# Sheet1.net
KiCad netlist of a schematic drawn in Altium Designer
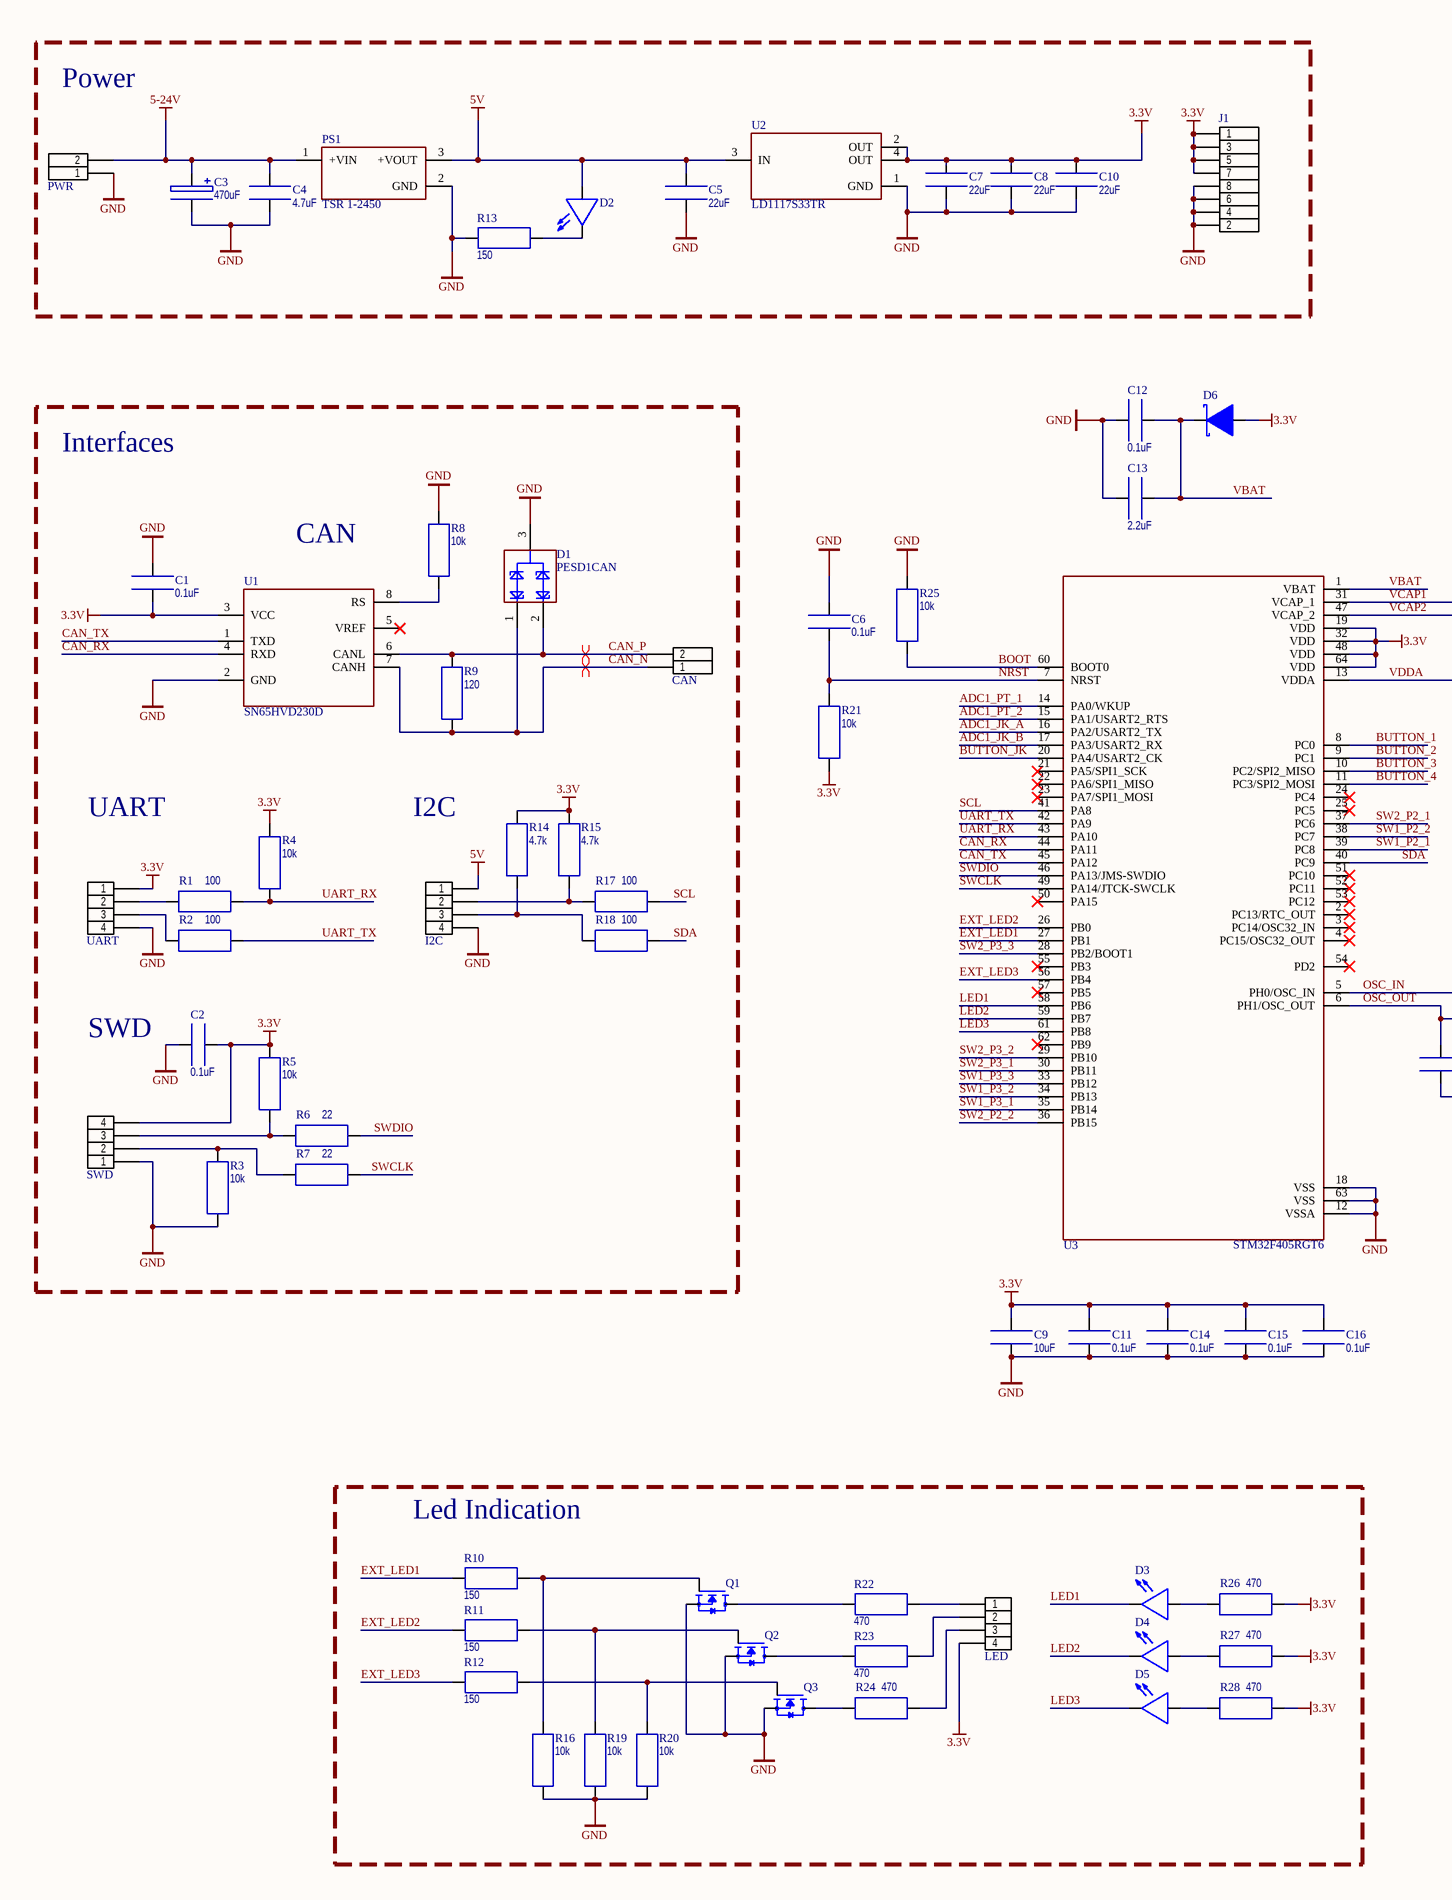
[diagram p0: Sheet1.SchDoc, left]
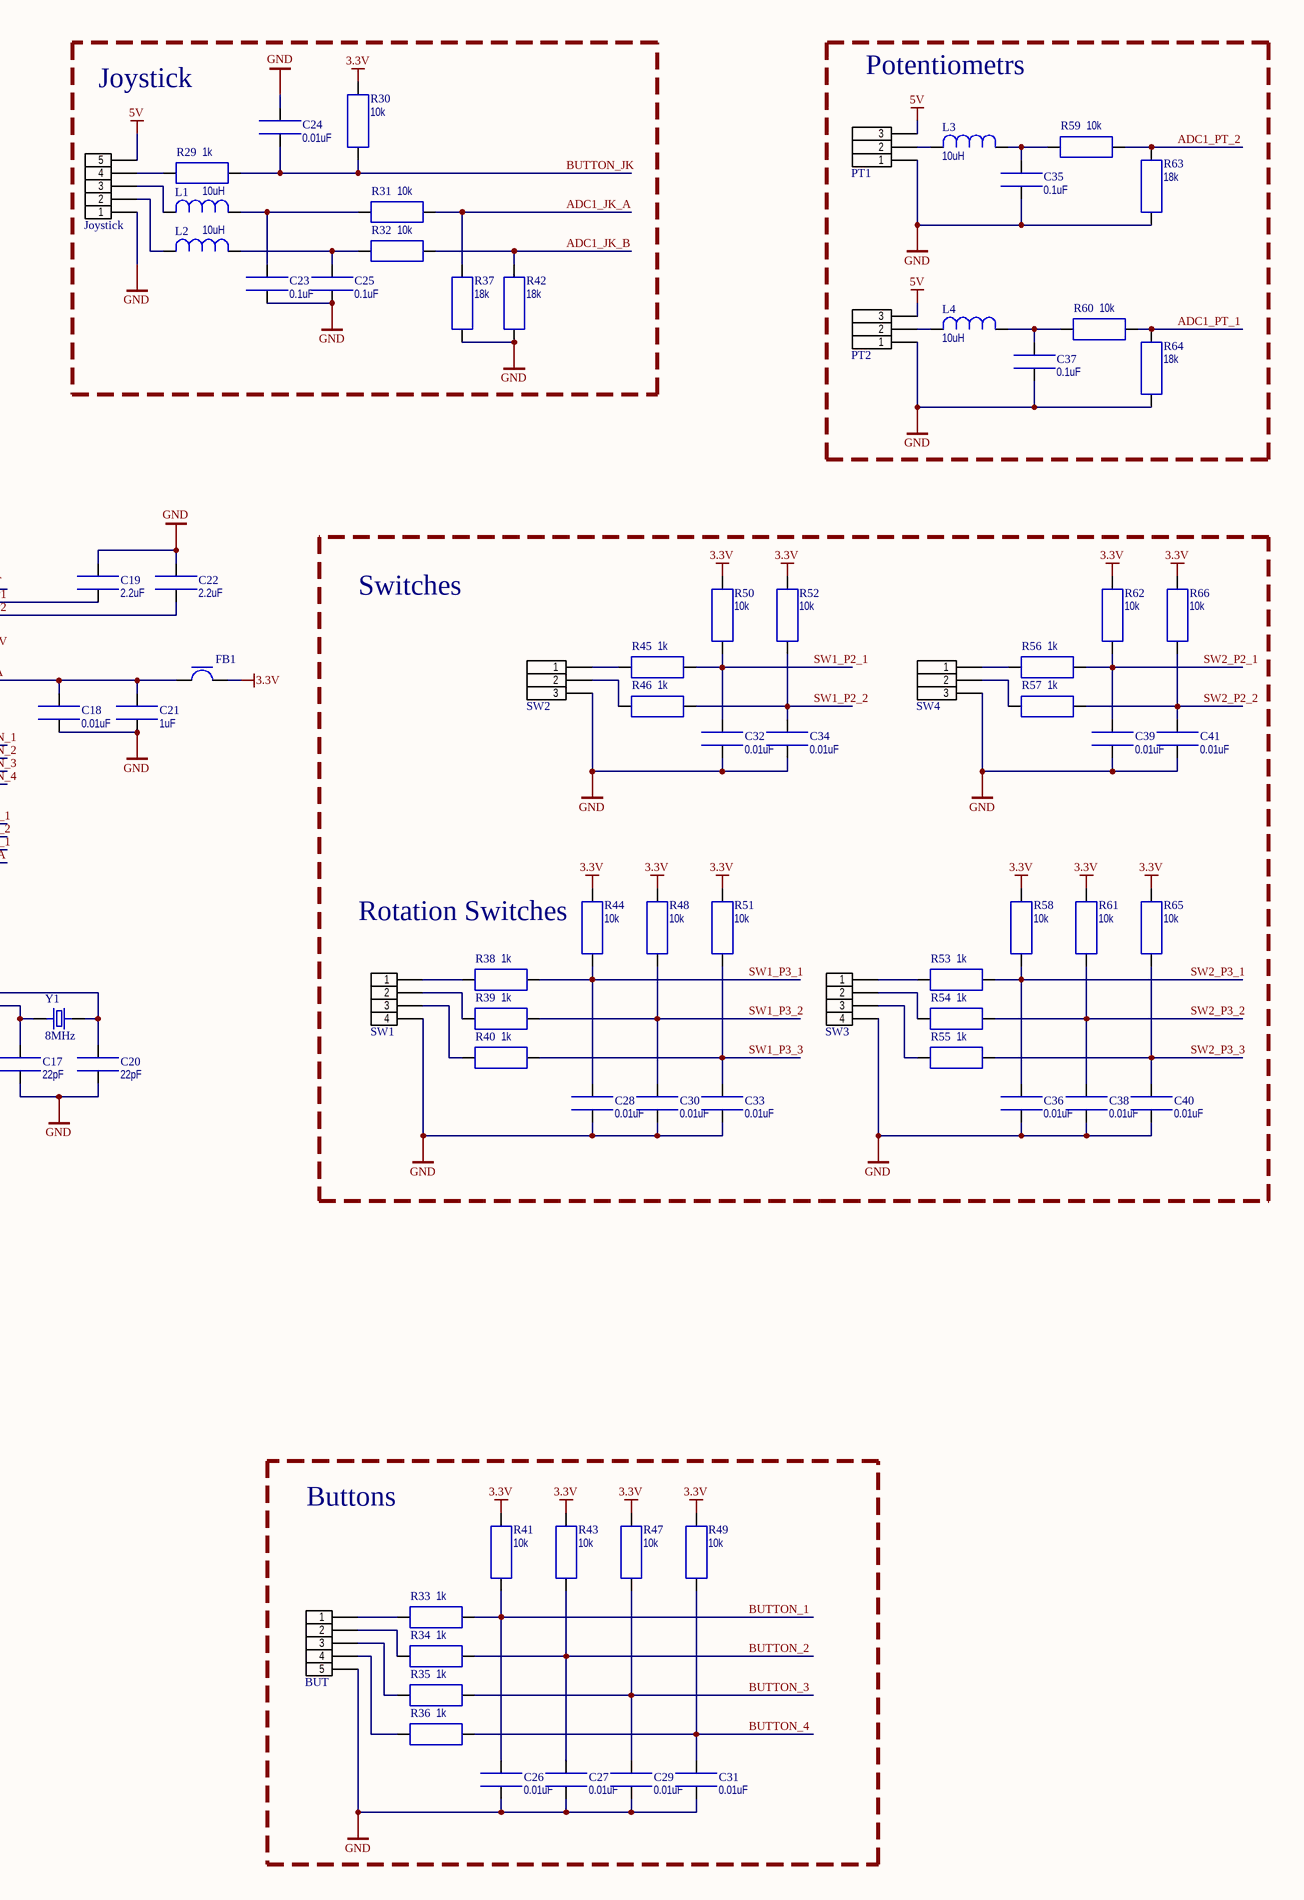
[diagram p1: Sheet1.SchDoc, right]

(export (version "E")
  (design (tool "Eeschema 10.0.6"))
  (components
    (comp (ref "BUT")
      (value "B5B-XH-A")
      (footprint "JST_B5B-XH-A")
      (description "Connector Header Through Hole 5 position 0.098 (2.50mm)")
      (fields (field (name "MF") "JST Sales"))
      (libsource (lib "connector") (part "B5B-XH-A"))
    )
    (comp (ref "C1") (value "0.1uF") (footprint "CAP 0603") (libsource (lib "passive") (part "CAP 0603")))
    (comp (ref "C2") (value "0.1uF") (footprint "CAP 0603") (libsource (lib "passive") (part "CAP 0603")))
    (comp (ref "C3") (value "470uF") (footprint "ECAP G") (libsource (lib "passive") (part "ECAP")))
    (comp (ref "C4") (value "4.7uF") (footprint "CAP 0603") (libsource (lib "passive") (part "CAP 0603")))
    (comp (ref "C5") (value "22uF") (footprint "CAP 0805") (libsource (lib "passive") (part "CAP 0805")))
    (comp (ref "C6") (value "0.1uF") (footprint "CAP 0603") (libsource (lib "passive") (part "CAP 0603")))
    (comp (ref "C7") (value "22uF") (footprint "CAP 0805") (libsource (lib "passive") (part "CAP 0805")))
    (comp (ref "C8") (value "22uF") (footprint "CAP 0805") (libsource (lib "passive") (part "CAP 0805")))
    (comp (ref "C9") (value "10uF") (footprint "CAP 0805") (libsource (lib "passive") (part "CAP 0805")))
    (comp (ref "C10") (value "22uF") (footprint "CAP 0805") (libsource (lib "passive") (part "CAP 0805")))
    (comp (ref "C11") (value "0.1uF") (footprint "CAP 0603") (libsource (lib "passive") (part "CAP 0603")))
    (comp (ref "C12") (value "0.1uF") (footprint "CAP 0603") (libsource (lib "passive") (part "CAP 0603")))
    (comp (ref "C13") (value "2.2uF") (footprint "CAP 0603") (libsource (lib "passive") (part "CAP 0603")))
    (comp (ref "C14") (value "0.1uF") (footprint "CAP 0603") (libsource (lib "passive") (part "CAP 0603")))
    (comp (ref "C15") (value "0.1uF") (footprint "CAP 0603") (libsource (lib "passive") (part "CAP 0603")))
    (comp (ref "C16") (value "0.1uF") (footprint "CAP 0603") (libsource (lib "passive") (part "CAP 0603")))
    (comp (ref "C17") (value "22pF") (footprint "CAP 0603") (libsource (lib "passive") (part "CAP 0603")))
    (comp (ref "C18") (value "0.01uF") (footprint "CAP 0603") (libsource (lib "passive") (part "CAP 0603")))
    (comp (ref "C19") (value "2.2uF") (footprint "CAP 0603") (libsource (lib "passive") (part "CAP 0603")))
    (comp (ref "C20") (value "22pF") (footprint "CAP 0603") (libsource (lib "passive") (part "CAP 0603")))
    (comp (ref "C21") (value "1uF") (footprint "CAP 0603") (libsource (lib "passive") (part "CAP 0603")))
    (comp (ref "C22") (value "2.2uF") (footprint "CAP 0603") (libsource (lib "passive") (part "CAP 0603")))
    (comp (ref "C23") (value "0.1uF") (footprint "CAP 0603") (libsource (lib "passive") (part "CAP 0603")))
    (comp (ref "C24") (value "0.01uF") (footprint "CAP 0603") (libsource (lib "passive") (part "CAP 0603")))
    (comp (ref "C25") (value "0.1uF") (footprint "CAP 0603") (libsource (lib "passive") (part "CAP 0603")))
    (comp (ref "C26") (value "0.01uF") (footprint "CAP 0603") (libsource (lib "passive") (part "CAP 0603")))
    (comp (ref "C27") (value "0.01uF") (footprint "CAP 0603") (libsource (lib "passive") (part "CAP 0603")))
    (comp (ref "C28") (value "0.01uF") (footprint "CAP 0603") (libsource (lib "passive") (part "CAP 0603")))
    (comp (ref "C29") (value "0.01uF") (footprint "CAP 0603") (libsource (lib "passive") (part "CAP 0603")))
    (comp (ref "C30") (value "0.01uF") (footprint "CAP 0603") (libsource (lib "passive") (part "CAP 0603")))
    (comp (ref "C31") (value "0.01uF") (footprint "CAP 0603") (libsource (lib "passive") (part "CAP 0603")))
    (comp (ref "C32") (value "0.01uF") (footprint "CAP 0603") (libsource (lib "passive") (part "CAP 0603")))
    (comp (ref "C33") (value "0.01uF") (footprint "CAP 0603") (libsource (lib "passive") (part "CAP 0603")))
    (comp (ref "C34") (value "0.01uF") (footprint "CAP 0603") (libsource (lib "passive") (part "CAP 0603")))
    (comp (ref "C35") (value "0.1uF") (footprint "CAP 0603") (libsource (lib "passive") (part "CAP 0603")))
    (comp (ref "C36") (value "0.01uF") (footprint "CAP 0603") (libsource (lib "passive") (part "CAP 0603")))
    (comp (ref "C37") (value "0.1uF") (footprint "CAP 0603") (libsource (lib "passive") (part "CAP 0603")))
    (comp (ref "C38") (value "0.01uF") (footprint "CAP 0603") (libsource (lib "passive") (part "CAP 0603")))
    (comp (ref "C39") (value "0.01uF") (footprint "CAP 0603") (libsource (lib "passive") (part "CAP 0603")))
    (comp (ref "C40") (value "0.01uF") (footprint "CAP 0603") (libsource (lib "passive") (part "CAP 0603")))
    (comp (ref "C41") (value "0.01uF") (footprint "CAP 0603") (libsource (lib "passive") (part "CAP 0603")))
    (comp (ref "CAN")
      (value "B2B-XH-A")
      (footprint "JST_B2B-XH-A")
      (description "Connector Header Through Hole 2 position 0.098 (2.50mm)")
      (fields (field (name "MF") "JST Sales") (field (name "MP") "B2B-XH-A(LF)(SN)"))
      (libsource (lib "connector") (part "B2B-XH-A"))
    )
    (comp (ref "D1")
      (value "PESD1CAN")
      (footprint "SOT23-3")
      (description "50V Clamp 3A (8/20Âµs) Ipp Tvs Diode Surface Mount SOT-323")
      (fields (field (name "MF") "Nexperia USA"))
      (libsource (lib "active") (part "PESD1CAN"))
    )
    (comp (ref "D2")
      (value "LED 0603")
      (footprint "LED 0603")
      (description "Green 560nm LED Indication - Discrete 2.2V 0603 (1608 Metric)")
      (fields (field (name "MF") "Rohm") (field (name "MP") "SML-D12P8WT86"))
      (libsource (lib "") (part "LED 0603_1"))
    )
    (comp (ref "D3")
      (value "LED 0603")
      (footprint "LED 0603")
      (description "Green 560nm LED Indication - Discrete 2.2V 0603 (1608 Metric)")
      (fields (field (name "MF") "Rohm") (field (name "MP") "SML-D12P8WT86"))
      (libsource (lib "active") (part "LED 0603"))
    )
    (comp (ref "D4")
      (value "LED 0603")
      (footprint "LED 0603")
      (description "Green 560nm LED Indication - Discrete 2.2V 0603 (1608 Metric)")
      (fields (field (name "MF") "Rohm") (field (name "MP") "SML-D12P8WT86"))
      (libsource (lib "active") (part "LED 0603"))
    )
    (comp (ref "D5")
      (value "LED 0603")
      (footprint "LED 0603")
      (description "Green 560nm LED Indication - Discrete 2.2V 0603 (1608 Metric)")
      (fields (field (name "MF") "Rohm") (field (name "MP") "SML-D12P8WT86"))
      (libsource (lib "active") (part "LED 0603"))
    )
    (comp (ref "D6")
      (value "SM5819PL")
      (footprint "SOD-123FL")
      (description "Schottky Diode, 40V, 1A")
      (libsource (lib "active") (part "SM5819PL"))
    )
    (comp (ref "FB1")
      (value "Ferrite bead 0603")
      (footprint "Ferrite bead 0603")
      (libsource (lib "passive") (part "Ferrite bead 0603"))
    )
    (comp (ref "I2C")
      (value "B4B-XH-A")
      (footprint "JST_B4B-XH-A")
      (description "Connector Header Through Hole 4 position 0.098 (2.50mm)")
      (fields (field (name "MF") "JST Sales"))
      (libsource (lib "connector") (part "B4B-XH-A"))
    )
    (comp (ref "J1")
      (value "Pin Header 2x4")
      (footprint "Pin Header 2x4")
      (description "Connector Header Through Hole 8 position 0.100 (2.54mm)")
      (fields (field (name "MF") "Samtec") (field (name "MP") "MTSW-104-07-T-D-240-LL"))
      (libsource (lib "connector") (part "Pin Header 2x4"))
    )
    (comp (ref "Joystick")
      (value "B5B-XH-A")
      (footprint "JST_B5B-XH-A")
      (description "Connector Header Through Hole 5 position 0.098 (2.50mm)")
      (fields (field (name "MF") "JST Sales"))
      (libsource (lib "connector") (part "B5B-XH-A"))
    )
    (comp (ref "L1") (value "10uH") (footprint "L 0603") (libsource (lib "passive") (part "L 0603")))
    (comp (ref "L2") (value "10uH") (footprint "L 0603") (libsource (lib "passive") (part "L 0603")))
    (comp (ref "L3") (value "10uH") (footprint "L 0603") (libsource (lib "passive") (part "L 0603")))
    (comp (ref "L4") (value "10uH") (footprint "L 0603") (libsource (lib "passive") (part "L 0603")))
    (comp (ref "LED")
      (value "B4B-XH-A")
      (footprint "JST_B4B-XH-A")
      (description "Connector Header Through Hole 4 position 0.098 (2.50mm)")
      (fields (field (name "MF") "JST Sales"))
      (libsource (lib "connector") (part "B4B-XH-A"))
    )
    (comp (ref "PS1")
      (value "TSR 1-2450")
      (footprint "SIP3")
      (fields (field (name "MF") "Traco Power") (field (name "MP") "TSR_1-2450"))
      (libsource (lib "mcu") (part "TSR 1-2450"))
    )
    (comp (ref "PT1")
      (value "B3B-XH-A")
      (footprint "JST_B3B-XH-A")
      (description "Connector Header Through Hole 3 position 0.098 (2.50mm)")
      (fields (field (name "MF") "JST Sales"))
      (libsource (lib "connector") (part "B3B-XH-A"))
    )
    (comp (ref "PT2")
      (value "B3B-XH-A")
      (footprint "JST_B3B-XH-A")
      (description "Connector Header Through Hole 3 position 0.098 (2.50mm)")
      (fields (field (name "MF") "JST Sales"))
      (libsource (lib "connector") (part "B3B-XH-A"))
    )
    (comp (ref "PWR")
      (value "B2B-XH-A")
      (footprint "JST_B2B-XH-A")
      (description "Connector Header Through Hole 2 position 0.098 (2.50mm)")
      (fields (field (name "MF") "JST Sales") (field (name "MP") "B2B-XH-A(LF)(SN)"))
      (libsource (lib "") (part "B2B-XH-A_1"))
    )
    (comp (ref "Q1")
      (value "MMFTN20")
      (footprint "SOT23-3")
      (description "MOSFET, SOT-23, N, 50V, 0.1A, 15â„¦, 150Â°C")
      (fields (field (name "MF") "Diotec Semiconductor"))
      (libsource (lib "active") (part "MMFTN20"))
    )
    (comp (ref "Q2")
      (value "MMFTN20")
      (footprint "SOT23-3")
      (description "MOSFET, SOT-23, N, 50V, 0.1A, 15â„¦, 150Â°C")
      (fields (field (name "MF") "Diotec Semiconductor"))
      (libsource (lib "active") (part "MMFTN20"))
    )
    (comp (ref "Q3")
      (value "MMFTN20")
      (footprint "SOT23-3")
      (description "MOSFET, SOT-23, N, 50V, 0.1A, 15â„¦, 150Â°C")
      (fields (field (name "MF") "Diotec Semiconductor"))
      (libsource (lib "active") (part "MMFTN20"))
    )
    (comp (ref "R1") (value "100") (footprint "RES 0603") (libsource (lib "passive") (part "RES 0603")))
    (comp (ref "R2") (value "100") (footprint "RES 0603") (libsource (lib "passive") (part "RES 0603")))
    (comp (ref "R3") (value "10k") (footprint "RES 0603") (libsource (lib "passive") (part "RES 0603")))
    (comp (ref "R4") (value "10k") (footprint "RES 0603") (libsource (lib "passive") (part "RES 0603")))
    (comp (ref "R5") (value "10k") (footprint "RES 0603") (libsource (lib "passive") (part "RES 0603")))
    (comp (ref "R6") (value "22") (footprint "RES 0603") (libsource (lib "passive") (part "RES 0603")))
    (comp (ref "R7") (value "22") (footprint "RES 0603") (libsource (lib "passive") (part "RES 0603")))
    (comp (ref "R8") (value "10k") (footprint "RES 0603") (libsource (lib "passive") (part "RES 0603")))
    (comp (ref "R9") (value "120") (footprint "RES 0603") (libsource (lib "passive") (part "RES 0603")))
    (comp (ref "R10") (value "150") (footprint "RES 0603") (libsource (lib "passive") (part "RES 0603")))
    (comp (ref "R11") (value "150") (footprint "RES 0603") (libsource (lib "passive") (part "RES 0603")))
    (comp (ref "R12") (value "150") (footprint "RES 0603") (libsource (lib "passive") (part "RES 0603")))
    (comp (ref "R13") (value "150") (footprint "RES 0603") (libsource (lib "passive") (part "RES 0603")))
    (comp (ref "R14") (value "4.7k") (footprint "RES 0603") (libsource (lib "passive") (part "RES 0603")))
    (comp (ref "R15") (value "4.7k") (footprint "RES 0603") (libsource (lib "passive") (part "RES 0603")))
    (comp (ref "R16") (value "10k") (footprint "RES 0603") (libsource (lib "passive") (part "RES 0603")))
    (comp (ref "R17") (value "100") (footprint "RES 0603") (libsource (lib "passive") (part "RES 0603")))
    (comp (ref "R18") (value "100") (footprint "RES 0603") (libsource (lib "passive") (part "RES 0603")))
    (comp (ref "R19") (value "10k") (footprint "RES 0603") (libsource (lib "passive") (part "RES 0603")))
    (comp (ref "R20") (value "10k") (footprint "RES 0603") (libsource (lib "passive") (part "RES 0603")))
    (comp (ref "R21") (value "10k") (footprint "RES 0603") (libsource (lib "passive") (part "RES 0603")))
    (comp (ref "R22") (value "470") (footprint "RES 0603") (libsource (lib "passive") (part "RES 0603")))
    (comp (ref "R23") (value "470") (footprint "RES 0603") (libsource (lib "passive") (part "RES 0603")))
    (comp (ref "R24") (value "470") (footprint "RES 0603") (libsource (lib "passive") (part "RES 0603")))
    (comp (ref "R25") (value "10k") (footprint "RES 0603") (libsource (lib "passive") (part "RES 0603")))
    (comp (ref "R26") (value "470") (footprint "RES 0603") (libsource (lib "passive") (part "RES 0603")))
    (comp (ref "R27") (value "470") (footprint "RES 0603") (libsource (lib "passive") (part "RES 0603")))
    (comp (ref "R28") (value "470") (footprint "RES 0603") (libsource (lib "passive") (part "RES 0603")))
    (comp (ref "R29") (value "1k") (footprint "RES 0603") (libsource (lib "passive") (part "RES 0603")))
    (comp (ref "R30") (value "10k") (footprint "RES 0603") (libsource (lib "passive") (part "RES 0603")))
    (comp (ref "R31") (value "10k") (footprint "RES 0603") (libsource (lib "passive") (part "RES 0603")))
    (comp (ref "R32") (value "10k") (footprint "RES 0603") (libsource (lib "passive") (part "RES 0603")))
    (comp (ref "R33") (value "1k") (footprint "RES 0603") (libsource (lib "passive") (part "RES 0603")))
    (comp (ref "R34") (value "1k") (footprint "RES 0603") (libsource (lib "passive") (part "RES 0603")))
    (comp (ref "R35") (value "1k") (footprint "RES 0603") (libsource (lib "passive") (part "RES 0603")))
    (comp (ref "R36") (value "1k") (footprint "RES 0603") (libsource (lib "passive") (part "RES 0603")))
    (comp (ref "R37") (value "18k") (footprint "RES 0603") (libsource (lib "passive") (part "RES 0603")))
    (comp (ref "R38") (value "1k") (footprint "RES 0603") (libsource (lib "passive") (part "RES 0603")))
    (comp (ref "R39") (value "1k") (footprint "RES 0603") (libsource (lib "passive") (part "RES 0603")))
    (comp (ref "R40") (value "1k") (footprint "RES 0603") (libsource (lib "passive") (part "RES 0603")))
    (comp (ref "R41") (value "10k") (footprint "RES 0603") (libsource (lib "passive") (part "RES 0603")))
    (comp (ref "R42") (value "18k") (footprint "RES 0603") (libsource (lib "passive") (part "RES 0603")))
    (comp (ref "R43") (value "10k") (footprint "RES 0603") (libsource (lib "passive") (part "RES 0603")))
    (comp (ref "R44") (value "10k") (footprint "RES 0603") (libsource (lib "passive") (part "RES 0603")))
    (comp (ref "R45") (value "1k") (footprint "RES 0603") (libsource (lib "passive") (part "RES 0603")))
    (comp (ref "R46") (value "1k") (footprint "RES 0603") (libsource (lib "passive") (part "RES 0603")))
    (comp (ref "R47") (value "10k") (footprint "RES 0603") (libsource (lib "passive") (part "RES 0603")))
    (comp (ref "R48") (value "10k") (footprint "RES 0603") (libsource (lib "passive") (part "RES 0603")))
    (comp (ref "R49") (value "10k") (footprint "RES 0603") (libsource (lib "passive") (part "RES 0603")))
    (comp (ref "R50") (value "10k") (footprint "RES 0603") (libsource (lib "passive") (part "RES 0603")))
    (comp (ref "R51") (value "10k") (footprint "RES 0603") (libsource (lib "passive") (part "RES 0603")))
    (comp (ref "R52") (value "10k") (footprint "RES 0603") (libsource (lib "passive") (part "RES 0603")))
    (comp (ref "R53") (value "1k") (footprint "RES 0603") (libsource (lib "passive") (part "RES 0603")))
    (comp (ref "R54") (value "1k") (footprint "RES 0603") (libsource (lib "passive") (part "RES 0603")))
    (comp (ref "R55") (value "1k") (footprint "RES 0603") (libsource (lib "passive") (part "RES 0603")))
    (comp (ref "R56") (value "1k") (footprint "RES 0603") (libsource (lib "passive") (part "RES 0603")))
    (comp (ref "R57") (value "1k") (footprint "RES 0603") (libsource (lib "passive") (part "RES 0603")))
    (comp (ref "R58") (value "10k") (footprint "RES 0603") (libsource (lib "passive") (part "RES 0603")))
    (comp (ref "R59") (value "10k") (footprint "RES 0603") (libsource (lib "passive") (part "RES 0603")))
    (comp (ref "R60") (value "10k") (footprint "RES 0603") (libsource (lib "passive") (part "RES 0603")))
    (comp (ref "R61") (value "10k") (footprint "RES 0603") (libsource (lib "passive") (part "RES 0603")))
    (comp (ref "R62") (value "10k") (footprint "RES 0603") (libsource (lib "passive") (part "RES 0603")))
    (comp (ref "R63") (value "18k") (footprint "RES 0603") (libsource (lib "passive") (part "RES 0603")))
    (comp (ref "R64") (value "18k") (footprint "RES 0603") (libsource (lib "passive") (part "RES 0603")))
    (comp (ref "R65") (value "10k") (footprint "RES 0603") (libsource (lib "passive") (part "RES 0603")))
    (comp (ref "R66") (value "10k") (footprint "RES 0603") (libsource (lib "passive") (part "RES 0603")))
    (comp (ref "SW1")
      (value "B4B-XH-A")
      (footprint "JST_B4B-XH-A")
      (description "Connector Header Through Hole 4 position 0.098 (2.50mm)")
      (fields (field (name "MF") "JST Sales"))
      (libsource (lib "connector") (part "B4B-XH-A"))
    )
    (comp (ref "SW2")
      (value "B3B-XH-A")
      (footprint "JST_B3B-XH-A")
      (description "Connector Header Through Hole 3 position 0.098 (2.50mm)")
      (fields (field (name "MF") "JST Sales"))
      (libsource (lib "") (part "B3B-XH-A_1"))
    )
    (comp (ref "SW3")
      (value "B4B-XH-A")
      (footprint "JST_B4B-XH-A")
      (description "Connector Header Through Hole 4 position 0.098 (2.50mm)")
      (fields (field (name "MF") "JST Sales"))
      (libsource (lib "connector") (part "B4B-XH-A"))
    )
    (comp (ref "SW4")
      (value "B3B-XH-A")
      (footprint "JST_B3B-XH-A")
      (description "Connector Header Through Hole 3 position 0.098 (2.50mm)")
      (fields (field (name "MF") "JST Sales"))
      (libsource (lib "") (part "B3B-XH-A_1"))
    )
    (comp (ref "SWD")
      (value "B4B-XH-A")
      (footprint "JST_B4B-XH-A")
      (description "Connector Header Through Hole 4 position 0.098 (2.50mm)")
      (fields (field (name "MF") "JST Sales"))
      (libsource (lib "connector") (part "B4B-XH-A"))
    )
    (comp (ref "U1")
      (value "SN65HVD230D")
      (footprint "SOIC8")
      (description "TI, 1/1 Transceiver Half CANbus 8-SO()")
      (libsource (lib "mcu") (part "SN65HVD230D"))
    )
    (comp (ref "U2")
      (value "LD1117S33TR")
      (footprint "SOT223")
      (description "Linear Voltage Regulator IC Positive Fixed 1 Output 800mA SOT-223")
      (fields (field (name "MF") "STMicroelectronics"))
      (libsource (lib "mcu") (part "LD1117S33TR"))
    )
    (comp (ref "U3")
      (value "STM32F405RGT6")
      (footprint "LQFP64")
      (fields (field (name "MF") "STMicroelectronics"))
      (libsource (lib "mcu") (part "STM32F405RGT6"))
    )
    (comp (ref "UART")
      (value "B4B-XH-A")
      (footprint "JST_B4B-XH-A")
      (description "Connector Header Through Hole 4 position 0.098 (2.50mm)")
      (fields (field (name "MF") "JST Sales"))
      (libsource (lib "connector") (part "B4B-XH-A"))
    )
    (comp (ref "Y1")
      (value "8MHz")
      (footprint "HC-49S")
      (description "Crystals 8MHz HC49S")
      (fields (field (name "MF") "ECS International") (field (name "MP") "ECS-17.1776-20-4"))
      (libsource (lib "other") (part "SJK-6B-8.000-16-30-50-C-50-H"))
    )
  )
  (nets
    (net (code "1") (name "/ADC1_JK_A") (class "Default")
      (node (ref "R31") (pin "2") (pintype "passive"))
      (node (ref "R37") (pin "2") (pintype "passive"))
      (node (ref "U3") (pin "16") (pinfunction "PA2/USART2_TX_16") (pintype "open_collector"))
    )
    (net (code "2") (name "/ADC1_JK_B") (class "Default")
      (node (ref "R32") (pin "2") (pintype "passive"))
      (node (ref "R42") (pin "2") (pintype "passive"))
      (node (ref "U3") (pin "17") (pinfunction "PA3/USART2_RX_17") (pintype "open_collector"))
    )
    (net (code "3") (name "/ADC1_PT_1") (class "Default")
      (node (ref "R60") (pin "2") (pintype "passive"))
      (node (ref "R64") (pin "2") (pintype "passive"))
      (node (ref "U3") (pin "14") (pinfunction "PA0/WKUP_14") (pintype "open_collector"))
    )
    (net (code "4") (name "/ADC1_PT_2") (class "Default")
      (node (ref "R59") (pin "2") (pintype "passive"))
      (node (ref "R63") (pin "2") (pintype "passive"))
      (node (ref "U3") (pin "15") (pinfunction "PA1/USART2_RTS_15") (pintype "open_collector"))
    )
    (net (code "5") (name "/BOOT") (class "Default")
      (node (ref "R25") (pin "1") (pintype "passive"))
      (node (ref "U3") (pin "60") (pinfunction "BOOT0_60") (pintype "open_collector"))
    )
    (net (code "6") (name "/BUTTON_1") (class "Default")
      (node (ref "C26") (pin "2") (pinfunction "2_2") (pintype "passive"))
      (node (ref "R33") (pin "2") (pintype "passive"))
      (node (ref "R41") (pin "1") (pintype "passive"))
      (node (ref "U3") (pin "8") (pinfunction "PC0_8") (pintype "open_collector"))
    )
    (net (code "7") (name "/BUTTON_2") (class "Default")
      (node (ref "C27") (pin "2") (pinfunction "2_2") (pintype "passive"))
      (node (ref "R34") (pin "2") (pintype "passive"))
      (node (ref "R43") (pin "1") (pintype "passive"))
      (node (ref "U3") (pin "9") (pinfunction "PC1_9") (pintype "open_collector"))
    )
    (net (code "8") (name "/BUTTON_3") (class "Default")
      (node (ref "C29") (pin "2") (pinfunction "2_2") (pintype "passive"))
      (node (ref "R35") (pin "2") (pintype "passive"))
      (node (ref "R47") (pin "1") (pintype "passive"))
      (node (ref "U3") (pin "10") (pinfunction "PC2/SPI2_MISO_10") (pintype "open_collector"))
    )
    (net (code "9") (name "/BUTTON_4") (class "Default")
      (node (ref "C31") (pin "2") (pinfunction "2_2") (pintype "passive"))
      (node (ref "R36") (pin "2") (pintype "passive"))
      (node (ref "R49") (pin "1") (pintype "passive"))
      (node (ref "U3") (pin "11") (pinfunction "PC3/SPI2_MOSI_11") (pintype "open_collector"))
    )
    (net (code "10") (name "/BUTTON_JK") (class "Default")
      (node (ref "C24") (pin "1") (pinfunction "1_1") (pintype "passive"))
      (node (ref "R29") (pin "2") (pintype "passive"))
      (node (ref "R30") (pin "1") (pintype "passive"))
      (node (ref "U3") (pin "20") (pinfunction "PA4/USART2_CK_20") (pintype "open_collector"))
    )
    (net (code "11") (name "/CAN_N") (class "Default")
      (node (ref "CAN") (pin "1") (pinfunction "1_1") (pintype "passive"))
      (node (ref "D1") (pin "1") (pinfunction "1_1") (pintype "passive"))
      (node (ref "R9") (pin "1") (pintype "passive"))
      (node (ref "U1") (pin "7") (pinfunction "CANH_7") (pintype "passive"))
    )
    (net (code "12") (name "/CAN_P") (class "Default")
      (node (ref "CAN") (pin "2") (pinfunction "2_2") (pintype "passive"))
      (node (ref "D1") (pin "2") (pinfunction "2_2") (pintype "passive"))
      (node (ref "R9") (pin "2") (pintype "passive"))
      (node (ref "U1") (pin "6") (pinfunction "CANL_6") (pintype "passive"))
    )
    (net (code "13") (name "/CAN_RX") (class "Default")
      (node (ref "U1") (pin "4") (pinfunction "RXD_4") (pintype "passive"))
      (node (ref "U3") (pin "44") (pinfunction "PA11_44") (pintype "open_collector"))
    )
    (net (code "14") (name "/CAN_TX") (class "Default")
      (node (ref "U1") (pin "1") (pinfunction "TXD_1") (pintype "passive"))
      (node (ref "U3") (pin "45") (pinfunction "PA12_45") (pintype "open_collector"))
    )
    (net (code "15") (name "/EXT_LED1") (class "Default")
      (node (ref "R10") (pin "2") (pintype "passive"))
      (node (ref "U3") (pin "27") (pinfunction "PB1_27") (pintype "open_collector"))
    )
    (net (code "16") (name "/EXT_LED2") (class "Default")
      (node (ref "R11") (pin "2") (pintype "passive"))
      (node (ref "U3") (pin "26") (pinfunction "PB0_26") (pintype "open_collector"))
    )
    (net (code "17") (name "/EXT_LED3") (class "Default")
      (node (ref "R12") (pin "2") (pintype "passive"))
      (node (ref "U3") (pin "56") (pinfunction "PB4_56") (pintype "open_collector"))
    )
    (net (code "18") (name "/LED1") (class "Default")
      (node (ref "D3") (pin "2") (pinfunction "2_2") (pintype "passive"))
      (node (ref "U3") (pin "58") (pinfunction "PB6_58") (pintype "open_collector"))
    )
    (net (code "19") (name "/LED2") (class "Default")
      (node (ref "D4") (pin "2") (pinfunction "2_2") (pintype "passive"))
      (node (ref "U3") (pin "59") (pinfunction "PB7_59") (pintype "open_collector"))
    )
    (net (code "20") (name "/LED3") (class "Default")
      (node (ref "D5") (pin "2") (pinfunction "2_2") (pintype "passive"))
      (node (ref "U3") (pin "61") (pinfunction "PB8_61") (pintype "open_collector"))
    )
    (net (code "21") (name "/NRST") (class "Default")
      (node (ref "C6") (pin "1") (pinfunction "1_1") (pintype "passive"))
      (node (ref "R21") (pin "2") (pintype "passive"))
      (node (ref "U3") (pin "7") (pinfunction "NRST_7") (pintype "open_collector"))
    )
    (net (code "22") (name "/OSC_IN") (class "Default")
      (node (ref "C20") (pin "2") (pinfunction "2_2") (pintype "passive"))
      (node (ref "U3") (pin "5") (pinfunction "PH0/OSC_IN_5") (pintype "open_collector"))
      (node (ref "Y1") (pin "2") (pinfunction "2_2") (pintype "passive"))
    )
    (net (code "23") (name "/OSC_OUT") (class "Default")
      (node (ref "C17") (pin "2") (pinfunction "2_2") (pintype "passive"))
      (node (ref "U3") (pin "6") (pinfunction "PH1/OSC_OUT_6") (pintype "open_collector"))
      (node (ref "Y1") (pin "1") (pinfunction "1_1") (pintype "passive"))
    )
    (net (code "24") (name "/SCL") (class "Default")
      (node (ref "R17") (pin "2") (pintype "passive"))
      (node (ref "U3") (pin "41") (pinfunction "PA8_41") (pintype "open_collector"))
    )
    (net (code "25") (name "/SDA") (class "Default")
      (node (ref "R18") (pin "2") (pintype "passive"))
      (node (ref "U3") (pin "40") (pinfunction "PC9_40") (pintype "open_collector"))
    )
    (net (code "26") (name "/SW1_P2_1") (class "Default")
      (node (ref "C32") (pin "2") (pinfunction "2_2") (pintype "passive"))
      (node (ref "R45") (pin "2") (pintype "passive"))
      (node (ref "R50") (pin "1") (pintype "passive"))
      (node (ref "U3") (pin "39") (pinfunction "PC8_39") (pintype "open_collector"))
    )
    (net (code "27") (name "/SW1_P2_2") (class "Default")
      (node (ref "C34") (pin "2") (pinfunction "2_2") (pintype "passive"))
      (node (ref "R46") (pin "2") (pintype "passive"))
      (node (ref "R52") (pin "1") (pintype "passive"))
      (node (ref "U3") (pin "38") (pinfunction "PC7_38") (pintype "open_collector"))
    )
    (net (code "28") (name "/SW1_P3_1") (class "Default")
      (node (ref "C28") (pin "2") (pinfunction "2_2") (pintype "passive"))
      (node (ref "R38") (pin "2") (pintype "passive"))
      (node (ref "R44") (pin "1") (pintype "passive"))
      (node (ref "U3") (pin "35") (pinfunction "PB14_35") (pintype "open_collector"))
    )
    (net (code "29") (name "/SW1_P3_2") (class "Default")
      (node (ref "C30") (pin "2") (pinfunction "2_2") (pintype "passive"))
      (node (ref "R39") (pin "2") (pintype "passive"))
      (node (ref "R48") (pin "1") (pintype "passive"))
      (node (ref "U3") (pin "34") (pinfunction "PB13_34") (pintype "open_collector"))
    )
    (net (code "30") (name "/SW1_P3_3") (class "Default")
      (node (ref "C33") (pin "2") (pinfunction "2_2") (pintype "passive"))
      (node (ref "R40") (pin "2") (pintype "passive"))
      (node (ref "R51") (pin "1") (pintype "passive"))
      (node (ref "U3") (pin "33") (pinfunction "PB12_33") (pintype "open_collector"))
    )
    (net (code "31") (name "/SW2_P2_1") (class "Default")
      (node (ref "C39") (pin "2") (pinfunction "2_2") (pintype "passive"))
      (node (ref "R56") (pin "2") (pintype "passive"))
      (node (ref "R62") (pin "1") (pintype "passive"))
      (node (ref "U3") (pin "37") (pinfunction "PC6_37") (pintype "open_collector"))
    )
    (net (code "32") (name "/SW2_P2_2") (class "Default")
      (node (ref "C41") (pin "2") (pinfunction "2_2") (pintype "passive"))
      (node (ref "R57") (pin "2") (pintype "passive"))
      (node (ref "R66") (pin "1") (pintype "passive"))
      (node (ref "U3") (pin "36") (pinfunction "PB15_36") (pintype "open_collector"))
    )
    (net (code "33") (name "/SW2_P3_1") (class "Default")
      (node (ref "C36") (pin "2") (pinfunction "2_2") (pintype "passive"))
      (node (ref "R53") (pin "2") (pintype "passive"))
      (node (ref "R58") (pin "1") (pintype "passive"))
      (node (ref "U3") (pin "30") (pinfunction "PB11_30") (pintype "open_collector"))
    )
    (net (code "34") (name "/SW2_P3_2") (class "Default")
      (node (ref "C38") (pin "2") (pinfunction "2_2") (pintype "passive"))
      (node (ref "R54") (pin "2") (pintype "passive"))
      (node (ref "R61") (pin "1") (pintype "passive"))
      (node (ref "U3") (pin "29") (pinfunction "PB10_29") (pintype "open_collector"))
    )
    (net (code "35") (name "/SW2_P3_3") (class "Default")
      (node (ref "C40") (pin "2") (pinfunction "2_2") (pintype "passive"))
      (node (ref "R55") (pin "2") (pintype "passive"))
      (node (ref "R65") (pin "1") (pintype "passive"))
      (node (ref "U3") (pin "28") (pinfunction "PB2/BOOT1_28") (pintype "open_collector"))
    )
    (net (code "36") (name "/SWCLK") (class "Default")
      (node (ref "R7") (pin "2") (pintype "passive"))
      (node (ref "U3") (pin "49") (pinfunction "PA14/JTCK-SWCLK_49") (pintype "open_collector"))
    )
    (net (code "37") (name "/SWDIO") (class "Default")
      (node (ref "R6") (pin "2") (pintype "passive"))
      (node (ref "U3") (pin "46") (pinfunction "PA13/JMS-SWDIO_46") (pintype "open_collector"))
    )
    (net (code "38") (name "/UART_RX") (class "Default")
      (node (ref "R1") (pin "2") (pintype "passive"))
      (node (ref "R4") (pin "1") (pintype "passive"))
      (node (ref "U3") (pin "43") (pinfunction "PA10_43") (pintype "open_collector"))
    )
    (net (code "39") (name "/UART_TX") (class "Default")
      (node (ref "R2") (pin "2") (pintype "passive"))
      (node (ref "U3") (pin "42") (pinfunction "PA9_42") (pintype "open_collector"))
    )
    (net (code "40") (name "/VBAT") (class "Default")
      (node (ref "C12") (pin "2") (pinfunction "2_2") (pintype "passive"))
      (node (ref "C13") (pin "1") (pinfunction "1_1") (pintype "passive"))
      (node (ref "D6") (pin "2") (pinfunction "2_2") (pintype "passive"))
      (node (ref "U3") (pin "1") (pinfunction "VBAT_1") (pintype "power_in"))
    )
    (net (code "41") (name "/VCAP1") (class "Default")
      (node (ref "C19") (pin "1") (pinfunction "1_1") (pintype "passive"))
      (node (ref "U3") (pin "31") (pinfunction "VCAP_1_31") (pintype "power_in"))
    )
    (net (code "42") (name "/VCAP2") (class "Default")
      (node (ref "C22") (pin "1") (pinfunction "1_1") (pintype "passive"))
      (node (ref "U3") (pin "47") (pinfunction "VCAP_2_47") (pintype "power_in"))
    )
    (net (code "43") (name "/VDDA") (class "Default")
      (node (ref "C18") (pin "2") (pinfunction "2_2") (pintype "passive"))
      (node (ref "C21") (pin "2") (pinfunction "2_2") (pintype "passive"))
      (node (ref "FB1") (pin "1") (pinfunction "1_1") (pintype "passive"))
      (node (ref "U3") (pin "13") (pinfunction "VDDA_13") (pintype "power_in"))
    )
    (net (code "44") (name "3.3V") (class "Default")
      (node (ref "C1") (pin "1") (pinfunction "1_1") (pintype "passive"))
      (node (ref "C10") (pin "2") (pinfunction "2_2") (pintype "passive"))
      (node (ref "C11") (pin "1") (pinfunction "1_1") (pintype "passive"))
      (node (ref "C14") (pin "1") (pinfunction "1_1") (pintype "passive"))
      (node (ref "C15") (pin "1") (pinfunction "1_1") (pintype "passive"))
      (node (ref "C16") (pin "1") (pinfunction "1_1") (pintype "passive"))
      (node (ref "C2") (pin "2") (pinfunction "2_2") (pintype "passive"))
      (node (ref "C7") (pin "2") (pinfunction "2_2") (pintype "passive"))
      (node (ref "C8") (pin "2") (pinfunction "2_2") (pintype "passive"))
      (node (ref "C9") (pin "1") (pinfunction "1_1") (pintype "passive"))
      (node (ref "D6") (pin "1") (pinfunction "1_1") (pintype "passive"))
      (node (ref "FB1") (pin "2") (pinfunction "2_2") (pintype "passive"))
      (node (ref "J1") (pin "1") (pinfunction "1_1") (pintype "passive"))
      (node (ref "J1") (pin "3") (pinfunction "3_3") (pintype "passive"))
      (node (ref "J1") (pin "5") (pinfunction "5_5") (pintype "passive"))
      (node (ref "J1") (pin "7") (pinfunction "7_7") (pintype "passive"))
      (node (ref "LED") (pin "4") (pinfunction "4_4") (pintype "passive"))
      (node (ref "R14") (pin "2") (pintype "passive"))
      (node (ref "R15") (pin "2") (pintype "passive"))
      (node (ref "R21") (pin "1") (pintype "passive"))
      (node (ref "R26") (pin "2") (pintype "passive"))
      (node (ref "R27") (pin "2") (pintype "passive"))
      (node (ref "R28") (pin "2") (pintype "passive"))
      (node (ref "R30") (pin "2") (pintype "passive"))
      (node (ref "R4") (pin "2") (pintype "passive"))
      (node (ref "R41") (pin "2") (pintype "passive"))
      (node (ref "R43") (pin "2") (pintype "passive"))
      (node (ref "R44") (pin "2") (pintype "passive"))
      (node (ref "R47") (pin "2") (pintype "passive"))
      (node (ref "R48") (pin "2") (pintype "passive"))
      (node (ref "R49") (pin "2") (pintype "passive"))
      (node (ref "R5") (pin "2") (pintype "passive"))
      (node (ref "R50") (pin "2") (pintype "passive"))
      (node (ref "R51") (pin "2") (pintype "passive"))
      (node (ref "R52") (pin "2") (pintype "passive"))
      (node (ref "R58") (pin "2") (pintype "passive"))
      (node (ref "R61") (pin "2") (pintype "passive"))
      (node (ref "R62") (pin "2") (pintype "passive"))
      (node (ref "R65") (pin "2") (pintype "passive"))
      (node (ref "R66") (pin "2") (pintype "passive"))
      (node (ref "SWD") (pin "4") (pinfunction "4_4") (pintype "passive"))
      (node (ref "U1") (pin "3") (pinfunction "VCC_3") (pintype "passive"))
      (node (ref "U2") (pin "2") (pinfunction "OUT_2") (pintype "power_in"))
      (node (ref "U2") (pin "4") (pinfunction "OUT_4") (pintype "power_in"))
      (node (ref "U3") (pin "19") (pinfunction "VDD_19") (pintype "power_in"))
      (node (ref "U3") (pin "32") (pinfunction "VDD_32") (pintype "power_in"))
      (node (ref "U3") (pin "48") (pinfunction "VDD_48") (pintype "power_in"))
      (node (ref "U3") (pin "64") (pinfunction "VDD_64") (pintype "power_in"))
      (node (ref "UART") (pin "1") (pinfunction "1_1") (pintype "passive"))
    )
    (net (code "45") (name "5-24V") (class "Default")
      (node (ref "C3") (pin "1") (pinfunction "1_1") (pintype "passive"))
      (node (ref "C4") (pin "2") (pinfunction "2_2") (pintype "passive"))
      (node (ref "PS1") (pin "1") (pinfunction "+VIN_1") (pintype "open_collector"))
      (node (ref "PWR") (pin "2") (pinfunction "2_2") (pintype "passive"))
    )
    (net (code "46") (name "5V") (class "Default")
      (node (ref "C5") (pin "2") (pinfunction "2_2") (pintype "passive"))
      (node (ref "D2") (pin "1") (pinfunction "1_1") (pintype "passive"))
      (node (ref "I2C") (pin "1") (pinfunction "1_1") (pintype "passive"))
      (node (ref "Joystick") (pin "5") (pinfunction "5_5") (pintype "passive"))
      (node (ref "PS1") (pin "3") (pinfunction "+VOUT_3") (pintype "open_collector"))
      (node (ref "PT1") (pin "3") (pinfunction "3_3") (pintype "passive"))
      (node (ref "PT2") (pin "3") (pinfunction "3_3") (pintype "passive"))
      (node (ref "U2") (pin "3") (pinfunction "IN_3") (pintype "open_collector"))
    )
    (net (code "47") (name "GND") (class "Default")
      (node (ref "BUT") (pin "5") (pinfunction "5_5") (pintype "passive"))
      (node (ref "C1") (pin "2") (pinfunction "2_2") (pintype "passive"))
      (node (ref "C10") (pin "1") (pinfunction "1_1") (pintype "passive"))
      (node (ref "C11") (pin "2") (pinfunction "2_2") (pintype "passive"))
      (node (ref "C12") (pin "1") (pinfunction "1_1") (pintype "passive"))
      (node (ref "C13") (pin "2") (pinfunction "2_2") (pintype "passive"))
      (node (ref "C14") (pin "2") (pinfunction "2_2") (pintype "passive"))
      (node (ref "C15") (pin "2") (pinfunction "2_2") (pintype "passive"))
      (node (ref "C16") (pin "2") (pinfunction "2_2") (pintype "passive"))
      (node (ref "C17") (pin "1") (pinfunction "1_1") (pintype "passive"))
      (node (ref "C18") (pin "1") (pinfunction "1_1") (pintype "passive"))
      (node (ref "C19") (pin "2") (pinfunction "2_2") (pintype "passive"))
      (node (ref "C2") (pin "1") (pinfunction "1_1") (pintype "passive"))
      (node (ref "C20") (pin "1") (pinfunction "1_1") (pintype "passive"))
      (node (ref "C21") (pin "1") (pinfunction "1_1") (pintype "passive"))
      (node (ref "C22") (pin "2") (pinfunction "2_2") (pintype "passive"))
      (node (ref "C23") (pin "1") (pinfunction "1_1") (pintype "passive"))
      (node (ref "C24") (pin "2") (pinfunction "2_2") (pintype "passive"))
      (node (ref "C25") (pin "1") (pinfunction "1_1") (pintype "passive"))
      (node (ref "C26") (pin "1") (pinfunction "1_1") (pintype "passive"))
      (node (ref "C27") (pin "1") (pinfunction "1_1") (pintype "passive"))
      (node (ref "C28") (pin "1") (pinfunction "1_1") (pintype "passive"))
      (node (ref "C29") (pin "1") (pinfunction "1_1") (pintype "passive"))
      (node (ref "C3") (pin "2") (pinfunction "2_2") (pintype "passive"))
      (node (ref "C30") (pin "1") (pinfunction "1_1") (pintype "passive"))
      (node (ref "C31") (pin "1") (pinfunction "1_1") (pintype "passive"))
      (node (ref "C32") (pin "1") (pinfunction "1_1") (pintype "passive"))
      (node (ref "C33") (pin "1") (pinfunction "1_1") (pintype "passive"))
      (node (ref "C34") (pin "1") (pinfunction "1_1") (pintype "passive"))
      (node (ref "C35") (pin "1") (pinfunction "1_1") (pintype "passive"))
      (node (ref "C36") (pin "1") (pinfunction "1_1") (pintype "passive"))
      (node (ref "C37") (pin "1") (pinfunction "1_1") (pintype "passive"))
      (node (ref "C38") (pin "1") (pinfunction "1_1") (pintype "passive"))
      (node (ref "C39") (pin "1") (pinfunction "1_1") (pintype "passive"))
      (node (ref "C4") (pin "1") (pinfunction "1_1") (pintype "passive"))
      (node (ref "C40") (pin "1") (pinfunction "1_1") (pintype "passive"))
      (node (ref "C41") (pin "1") (pinfunction "1_1") (pintype "passive"))
      (node (ref "C5") (pin "1") (pinfunction "1_1") (pintype "passive"))
      (node (ref "C6") (pin "2") (pinfunction "2_2") (pintype "passive"))
      (node (ref "C7") (pin "1") (pinfunction "1_1") (pintype "passive"))
      (node (ref "C8") (pin "1") (pinfunction "1_1") (pintype "passive"))
      (node (ref "C9") (pin "2") (pinfunction "2_2") (pintype "passive"))
      (node (ref "D1") (pin "3") (pinfunction "3_3") (pintype "passive"))
      (node (ref "I2C") (pin "4") (pinfunction "4_4") (pintype "passive"))
      (node (ref "J1") (pin "2") (pinfunction "2_2") (pintype "passive"))
      (node (ref "J1") (pin "4") (pinfunction "4_4") (pintype "passive"))
      (node (ref "J1") (pin "6") (pinfunction "6_6") (pintype "passive"))
      (node (ref "J1") (pin "8") (pinfunction "8_8") (pintype "passive"))
      (node (ref "Joystick") (pin "1") (pinfunction "1_1") (pintype "passive"))
      (node (ref "PS1") (pin "2") (pinfunction "GND_2") (pintype "power_in"))
      (node (ref "PT1") (pin "1") (pinfunction "1_1") (pintype "passive"))
      (node (ref "PT2") (pin "1") (pinfunction "1_1") (pintype "passive"))
      (node (ref "PWR") (pin "1") (pinfunction "1_1") (pintype "passive"))
      (node (ref "Q1") (pin "2") (pinfunction "S_2") (pintype "passive"))
      (node (ref "Q2") (pin "2") (pinfunction "S_2") (pintype "passive"))
      (node (ref "Q3") (pin "2") (pinfunction "S_2") (pintype "passive"))
      (node (ref "R13") (pin "1") (pintype "passive"))
      (node (ref "R16") (pin "1") (pintype "passive"))
      (node (ref "R19") (pin "1") (pintype "passive"))
      (node (ref "R20") (pin "1") (pintype "passive"))
      (node (ref "R25") (pin "2") (pintype "passive"))
      (node (ref "R3") (pin "1") (pintype "passive"))
      (node (ref "R37") (pin "1") (pintype "passive"))
      (node (ref "R42") (pin "1") (pintype "passive"))
      (node (ref "R63") (pin "1") (pintype "passive"))
      (node (ref "R64") (pin "1") (pintype "passive"))
      (node (ref "R8") (pin "2") (pintype "passive"))
      (node (ref "SW1") (pin "4") (pinfunction "4_4") (pintype "passive"))
      (node (ref "SW2") (pin "3") (pinfunction "3_3") (pintype "passive"))
      (node (ref "SW3") (pin "4") (pinfunction "4_4") (pintype "passive"))
      (node (ref "SW4") (pin "3") (pinfunction "3_3") (pintype "passive"))
      (node (ref "SWD") (pin "1") (pinfunction "1_1") (pintype "passive"))
      (node (ref "U1") (pin "2") (pinfunction "GND_2") (pintype "passive"))
      (node (ref "U2") (pin "1") (pinfunction "GND_1") (pintype "power_in"))
      (node (ref "U3") (pin "12") (pinfunction "VSSA_12") (pintype "power_in"))
      (node (ref "U3") (pin "18") (pinfunction "VSS_18") (pintype "power_in"))
      (node (ref "U3") (pin "63") (pinfunction "VSS_63") (pintype "power_in"))
      (node (ref "UART") (pin "4") (pinfunction "4_4") (pintype "passive"))
    )
    (net (code "48") (name "Net-(BUT-Pad1)") (class "Default")
      (node (ref "BUT") (pin "1") (pinfunction "1_1") (pintype "passive"))
      (node (ref "R33") (pin "1") (pintype "passive"))
    )
    (net (code "49") (name "Net-(BUT-Pad2)") (class "Default")
      (node (ref "BUT") (pin "2") (pinfunction "2_2") (pintype "passive"))
      (node (ref "R34") (pin "1") (pintype "passive"))
    )
    (net (code "50") (name "Net-(BUT-Pad3)") (class "Default")
      (node (ref "BUT") (pin "3") (pinfunction "3_3") (pintype "passive"))
      (node (ref "R35") (pin "1") (pintype "passive"))
    )
    (net (code "51") (name "Net-(BUT-Pad4)") (class "Default")
      (node (ref "BUT") (pin "4") (pinfunction "4_4") (pintype "passive"))
      (node (ref "R36") (pin "1") (pintype "passive"))
    )
    (net (code "52") (name "Net-(C23-Pad2)") (class "Default")
      (node (ref "C23") (pin "2") (pinfunction "2_2") (pintype "passive"))
      (node (ref "L1") (pin "2") (pinfunction "2_2") (pintype "passive"))
      (node (ref "R31") (pin "1") (pintype "passive"))
    )
    (net (code "53") (name "Net-(C25-Pad2)") (class "Default")
      (node (ref "C25") (pin "2") (pinfunction "2_2") (pintype "passive"))
      (node (ref "L2") (pin "2") (pinfunction "2_2") (pintype "passive"))
      (node (ref "R32") (pin "1") (pintype "passive"))
    )
    (net (code "54") (name "Net-(C35-Pad2)") (class "Default")
      (node (ref "C35") (pin "2") (pinfunction "2_2") (pintype "passive"))
      (node (ref "L3") (pin "2") (pinfunction "2_2") (pintype "passive"))
      (node (ref "R59") (pin "1") (pintype "passive"))
    )
    (net (code "55") (name "Net-(C37-Pad2)") (class "Default")
      (node (ref "C37") (pin "2") (pinfunction "2_2") (pintype "passive"))
      (node (ref "L4") (pin "2") (pinfunction "2_2") (pintype "passive"))
      (node (ref "R60") (pin "1") (pintype "passive"))
    )
    (net (code "56") (name "Net-(D2-Pad2)") (class "Default")
      (node (ref "D2") (pin "2") (pinfunction "2_2") (pintype "passive"))
      (node (ref "R13") (pin "2") (pintype "passive"))
    )
    (net (code "57") (name "Net-(D3-Pad1)") (class "Default")
      (node (ref "D3") (pin "1") (pinfunction "1_1") (pintype "passive"))
      (node (ref "R26") (pin "1") (pintype "passive"))
    )
    (net (code "58") (name "Net-(D4-Pad1)") (class "Default")
      (node (ref "D4") (pin "1") (pinfunction "1_1") (pintype "passive"))
      (node (ref "R27") (pin "1") (pintype "passive"))
    )
    (net (code "59") (name "Net-(D5-Pad1)") (class "Default")
      (node (ref "D5") (pin "1") (pinfunction "1_1") (pintype "passive"))
      (node (ref "R28") (pin "1") (pintype "passive"))
    )
    (net (code "60") (name "Net-(I2C-Pad2)") (class "Default")
      (node (ref "I2C") (pin "2") (pinfunction "2_2") (pintype "passive"))
      (node (ref "R15") (pin "1") (pintype "passive"))
      (node (ref "R17") (pin "1") (pintype "passive"))
    )
    (net (code "61") (name "Net-(I2C-Pad3)") (class "Default")
      (node (ref "I2C") (pin "3") (pinfunction "3_3") (pintype "passive"))
      (node (ref "R14") (pin "1") (pintype "passive"))
      (node (ref "R18") (pin "1") (pintype "passive"))
    )
    (net (code "62") (name "Net-(Joystick-Pad2)") (class "Default")
      (node (ref "Joystick") (pin "2") (pinfunction "2_2") (pintype "passive"))
      (node (ref "L2") (pin "1") (pinfunction "1_1") (pintype "passive"))
    )
    (net (code "63") (name "Net-(Joystick-Pad3)") (class "Default")
      (node (ref "Joystick") (pin "3") (pinfunction "3_3") (pintype "passive"))
      (node (ref "L1") (pin "1") (pinfunction "1_1") (pintype "passive"))
    )
    (net (code "64") (name "Net-(Joystick-Pad4)") (class "Default")
      (node (ref "Joystick") (pin "4") (pinfunction "4_4") (pintype "passive"))
      (node (ref "R29") (pin "1") (pintype "passive"))
    )
    (net (code "65") (name "Net-(L3-Pad1)") (class "Default")
      (node (ref "L3") (pin "1") (pinfunction "1_1") (pintype "passive"))
      (node (ref "PT1") (pin "2") (pinfunction "2_2") (pintype "passive"))
    )
    (net (code "66") (name "Net-(L4-Pad1)") (class "Default")
      (node (ref "L4") (pin "1") (pinfunction "1_1") (pintype "passive"))
      (node (ref "PT2") (pin "2") (pinfunction "2_2") (pintype "passive"))
    )
    (net (code "67") (name "Net-(LED-Pad1)") (class "Default")
      (node (ref "LED") (pin "1") (pinfunction "1_1") (pintype "passive"))
      (node (ref "R22") (pin "1") (pintype "passive"))
    )
    (net (code "68") (name "Net-(LED-Pad2)") (class "Default")
      (node (ref "LED") (pin "2") (pinfunction "2_2") (pintype "passive"))
      (node (ref "R23") (pin "1") (pintype "passive"))
    )
    (net (code "69") (name "Net-(LED-Pad3)") (class "Default")
      (node (ref "LED") (pin "3") (pinfunction "3_3") (pintype "passive"))
      (node (ref "R24") (pin "2") (pintype "passive"))
    )
    (net (code "70") (name "Net-(Q1-D)") (class "Default")
      (node (ref "Q1") (pin "3") (pinfunction "D_3") (pintype "passive"))
      (node (ref "R22") (pin "2") (pintype "passive"))
    )
    (net (code "71") (name "Net-(Q1-G)") (class "Default")
      (node (ref "Q1") (pin "1") (pinfunction "G_1") (pintype "passive"))
      (node (ref "R10") (pin "1") (pintype "passive"))
      (node (ref "R16") (pin "2") (pintype "passive"))
    )
    (net (code "72") (name "Net-(Q2-D)") (class "Default")
      (node (ref "Q2") (pin "3") (pinfunction "D_3") (pintype "passive"))
      (node (ref "R23") (pin "2") (pintype "passive"))
    )
    (net (code "73") (name "Net-(Q2-G)") (class "Default")
      (node (ref "Q2") (pin "1") (pinfunction "G_1") (pintype "passive"))
      (node (ref "R11") (pin "1") (pintype "passive"))
      (node (ref "R19") (pin "2") (pintype "passive"))
    )
    (net (code "74") (name "Net-(Q3-D)") (class "Default")
      (node (ref "Q3") (pin "3") (pinfunction "D_3") (pintype "passive"))
      (node (ref "R24") (pin "1") (pintype "passive"))
    )
    (net (code "75") (name "Net-(Q3-G)") (class "Default")
      (node (ref "Q3") (pin "1") (pinfunction "G_1") (pintype "passive"))
      (node (ref "R12") (pin "1") (pintype "passive"))
      (node (ref "R20") (pin "2") (pintype "passive"))
    )
    (net (code "76") (name "Net-(R1-Pad1)") (class "Default")
      (node (ref "R1") (pin "1") (pintype "passive"))
      (node (ref "UART") (pin "2") (pinfunction "2_2") (pintype "passive"))
    )
    (net (code "77") (name "Net-(R2-Pad1)") (class "Default")
      (node (ref "R2") (pin "1") (pintype "passive"))
      (node (ref "UART") (pin "3") (pinfunction "3_3") (pintype "passive"))
    )
    (net (code "78") (name "Net-(R3-Pad2)") (class "Default")
      (node (ref "R3") (pin "2") (pintype "passive"))
      (node (ref "R7") (pin "1") (pintype "passive"))
      (node (ref "SWD") (pin "2") (pinfunction "2_2") (pintype "passive"))
    )
    (net (code "79") (name "Net-(R5-Pad1)") (class "Default")
      (node (ref "R5") (pin "1") (pintype "passive"))
      (node (ref "R6") (pin "1") (pintype "passive"))
      (node (ref "SWD") (pin "3") (pinfunction "3_3") (pintype "passive"))
    )
    (net (code "80") (name "Net-(R38-Pad1)") (class "Default")
      (node (ref "R38") (pin "1") (pintype "passive"))
      (node (ref "SW1") (pin "1") (pinfunction "1_1") (pintype "passive"))
    )
    (net (code "81") (name "Net-(R39-Pad1)") (class "Default")
      (node (ref "R39") (pin "1") (pintype "passive"))
      (node (ref "SW1") (pin "2") (pinfunction "2_2") (pintype "passive"))
    )
    (net (code "82") (name "Net-(R40-Pad1)") (class "Default")
      (node (ref "R40") (pin "1") (pintype "passive"))
      (node (ref "SW1") (pin "3") (pinfunction "3_3") (pintype "passive"))
    )
    (net (code "83") (name "Net-(R45-Pad1)") (class "Default")
      (node (ref "R45") (pin "1") (pintype "passive"))
      (node (ref "SW2") (pin "1") (pinfunction "1_1") (pintype "passive"))
    )
    (net (code "84") (name "Net-(R46-Pad1)") (class "Default")
      (node (ref "R46") (pin "1") (pintype "passive"))
      (node (ref "SW2") (pin "2") (pinfunction "2_2") (pintype "passive"))
    )
    (net (code "85") (name "Net-(R53-Pad1)") (class "Default")
      (node (ref "R53") (pin "1") (pintype "passive"))
      (node (ref "SW3") (pin "1") (pinfunction "1_1") (pintype "passive"))
    )
    (net (code "86") (name "Net-(R54-Pad1)") (class "Default")
      (node (ref "R54") (pin "1") (pintype "passive"))
      (node (ref "SW3") (pin "2") (pinfunction "2_2") (pintype "passive"))
    )
    (net (code "87") (name "Net-(R55-Pad1)") (class "Default")
      (node (ref "R55") (pin "1") (pintype "passive"))
      (node (ref "SW3") (pin "3") (pinfunction "3_3") (pintype "passive"))
    )
    (net (code "88") (name "Net-(R56-Pad1)") (class "Default")
      (node (ref "R56") (pin "1") (pintype "passive"))
      (node (ref "SW4") (pin "1") (pinfunction "1_1") (pintype "passive"))
    )
    (net (code "89") (name "Net-(R57-Pad1)") (class "Default")
      (node (ref "R57") (pin "1") (pintype "passive"))
      (node (ref "SW4") (pin "2") (pinfunction "2_2") (pintype "passive"))
    )
    (net (code "90") (name "Net-(U1-RS)") (class "Default")
      (node (ref "R8") (pin "1") (pintype "passive"))
      (node (ref "U1") (pin "8") (pinfunction "RS_8") (pintype "passive"))
    )
    (net (code "91") (name "unconnected-(U1-VREF-Pad5)") (class "Default")
      (node (ref "U1") (pin "5") (pinfunction "VREF_5") (pintype "passive+no_connect"))
    )
    (net (code "92") (name "unconnected-(U3-PA5{slash}SPI1_SCK-Pad21)") (class "Default")
      (node (ref "U3") (pin "21") (pinfunction "PA5/SPI1_SCK_21") (pintype "open_collector+no_connect"))
    )
    (net (code "93") (name "unconnected-(U3-PA6{slash}SPI1_MISO-Pad22)") (class "Default")
      (node (ref "U3") (pin "22") (pinfunction "PA6/SPI1_MISO_22") (pintype "open_collector+no_connect"))
    )
    (net (code "94") (name "unconnected-(U3-PA7{slash}SPI1_MOSI-Pad23)") (class "Default")
      (node (ref "U3") (pin "23") (pinfunction "PA7/SPI1_MOSI_23") (pintype "open_collector+no_connect"))
    )
    (net (code "95") (name "unconnected-(U3-PA15-Pad50)") (class "Default")
      (node (ref "U3") (pin "50") (pinfunction "PA15_50") (pintype "open_collector+no_connect"))
    )
    (net (code "96") (name "unconnected-(U3-PB3-Pad55)") (class "Default")
      (node (ref "U3") (pin "55") (pinfunction "PB3_55") (pintype "open_collector+no_connect"))
    )
    (net (code "97") (name "unconnected-(U3-PB5-Pad57)") (class "Default")
      (node (ref "U3") (pin "57") (pinfunction "PB5_57") (pintype "open_collector+no_connect"))
    )
    (net (code "98") (name "unconnected-(U3-PB9-Pad62)") (class "Default")
      (node (ref "U3") (pin "62") (pinfunction "PB9_62") (pintype "open_collector+no_connect"))
    )
    (net (code "99") (name "unconnected-(U3-PC4-Pad24)") (class "Default")
      (node (ref "U3") (pin "24") (pinfunction "PC4_24") (pintype "open_collector+no_connect"))
    )
    (net (code "100") (name "unconnected-(U3-PC5-Pad25)") (class "Default")
      (node (ref "U3") (pin "25") (pinfunction "PC5_25") (pintype "open_collector+no_connect"))
    )
    (net (code "101") (name "unconnected-(U3-PC10-Pad51)") (class "Default")
      (node (ref "U3") (pin "51") (pinfunction "PC10_51") (pintype "open_collector+no_connect"))
    )
    (net (code "102") (name "unconnected-(U3-PC11-Pad52)") (class "Default")
      (node (ref "U3") (pin "52") (pinfunction "PC11_52") (pintype "open_collector+no_connect"))
    )
    (net (code "103") (name "unconnected-(U3-PC12-Pad53)") (class "Default")
      (node (ref "U3") (pin "53") (pinfunction "PC12_53") (pintype "open_collector+no_connect"))
    )
    (net (code "104") (name "unconnected-(U3-PC13{slash}RTC_OUT-Pad2)") (class "Default")
      (node (ref "U3") (pin "2") (pinfunction "PC13/RTC_OUT_2") (pintype "open_collector+no_connect"))
    )
    (net (code "105") (name "unconnected-(U3-PC14{slash}OSC32_IN-Pad3)") (class "Default")
      (node (ref "U3") (pin "3") (pinfunction "PC14/OSC32_IN_3") (pintype "open_collector+no_connect"))
    )
    (net (code "106") (name "unconnected-(U3-PC15{slash}OSC32_OUT-Pad4)") (class "Default")
      (node (ref "U3") (pin "4") (pinfunction "PC15/OSC32_OUT_4") (pintype "open_collector+no_connect"))
    )
    (net (code "107") (name "unconnected-(U3-PD2-Pad54)") (class "Default")
      (node (ref "U3") (pin "54") (pinfunction "PD2_54") (pintype "open_collector+no_connect"))
    )
  )
)
